# MB1137.net
KiCad netlist of a schematic drawn in Altium Designer
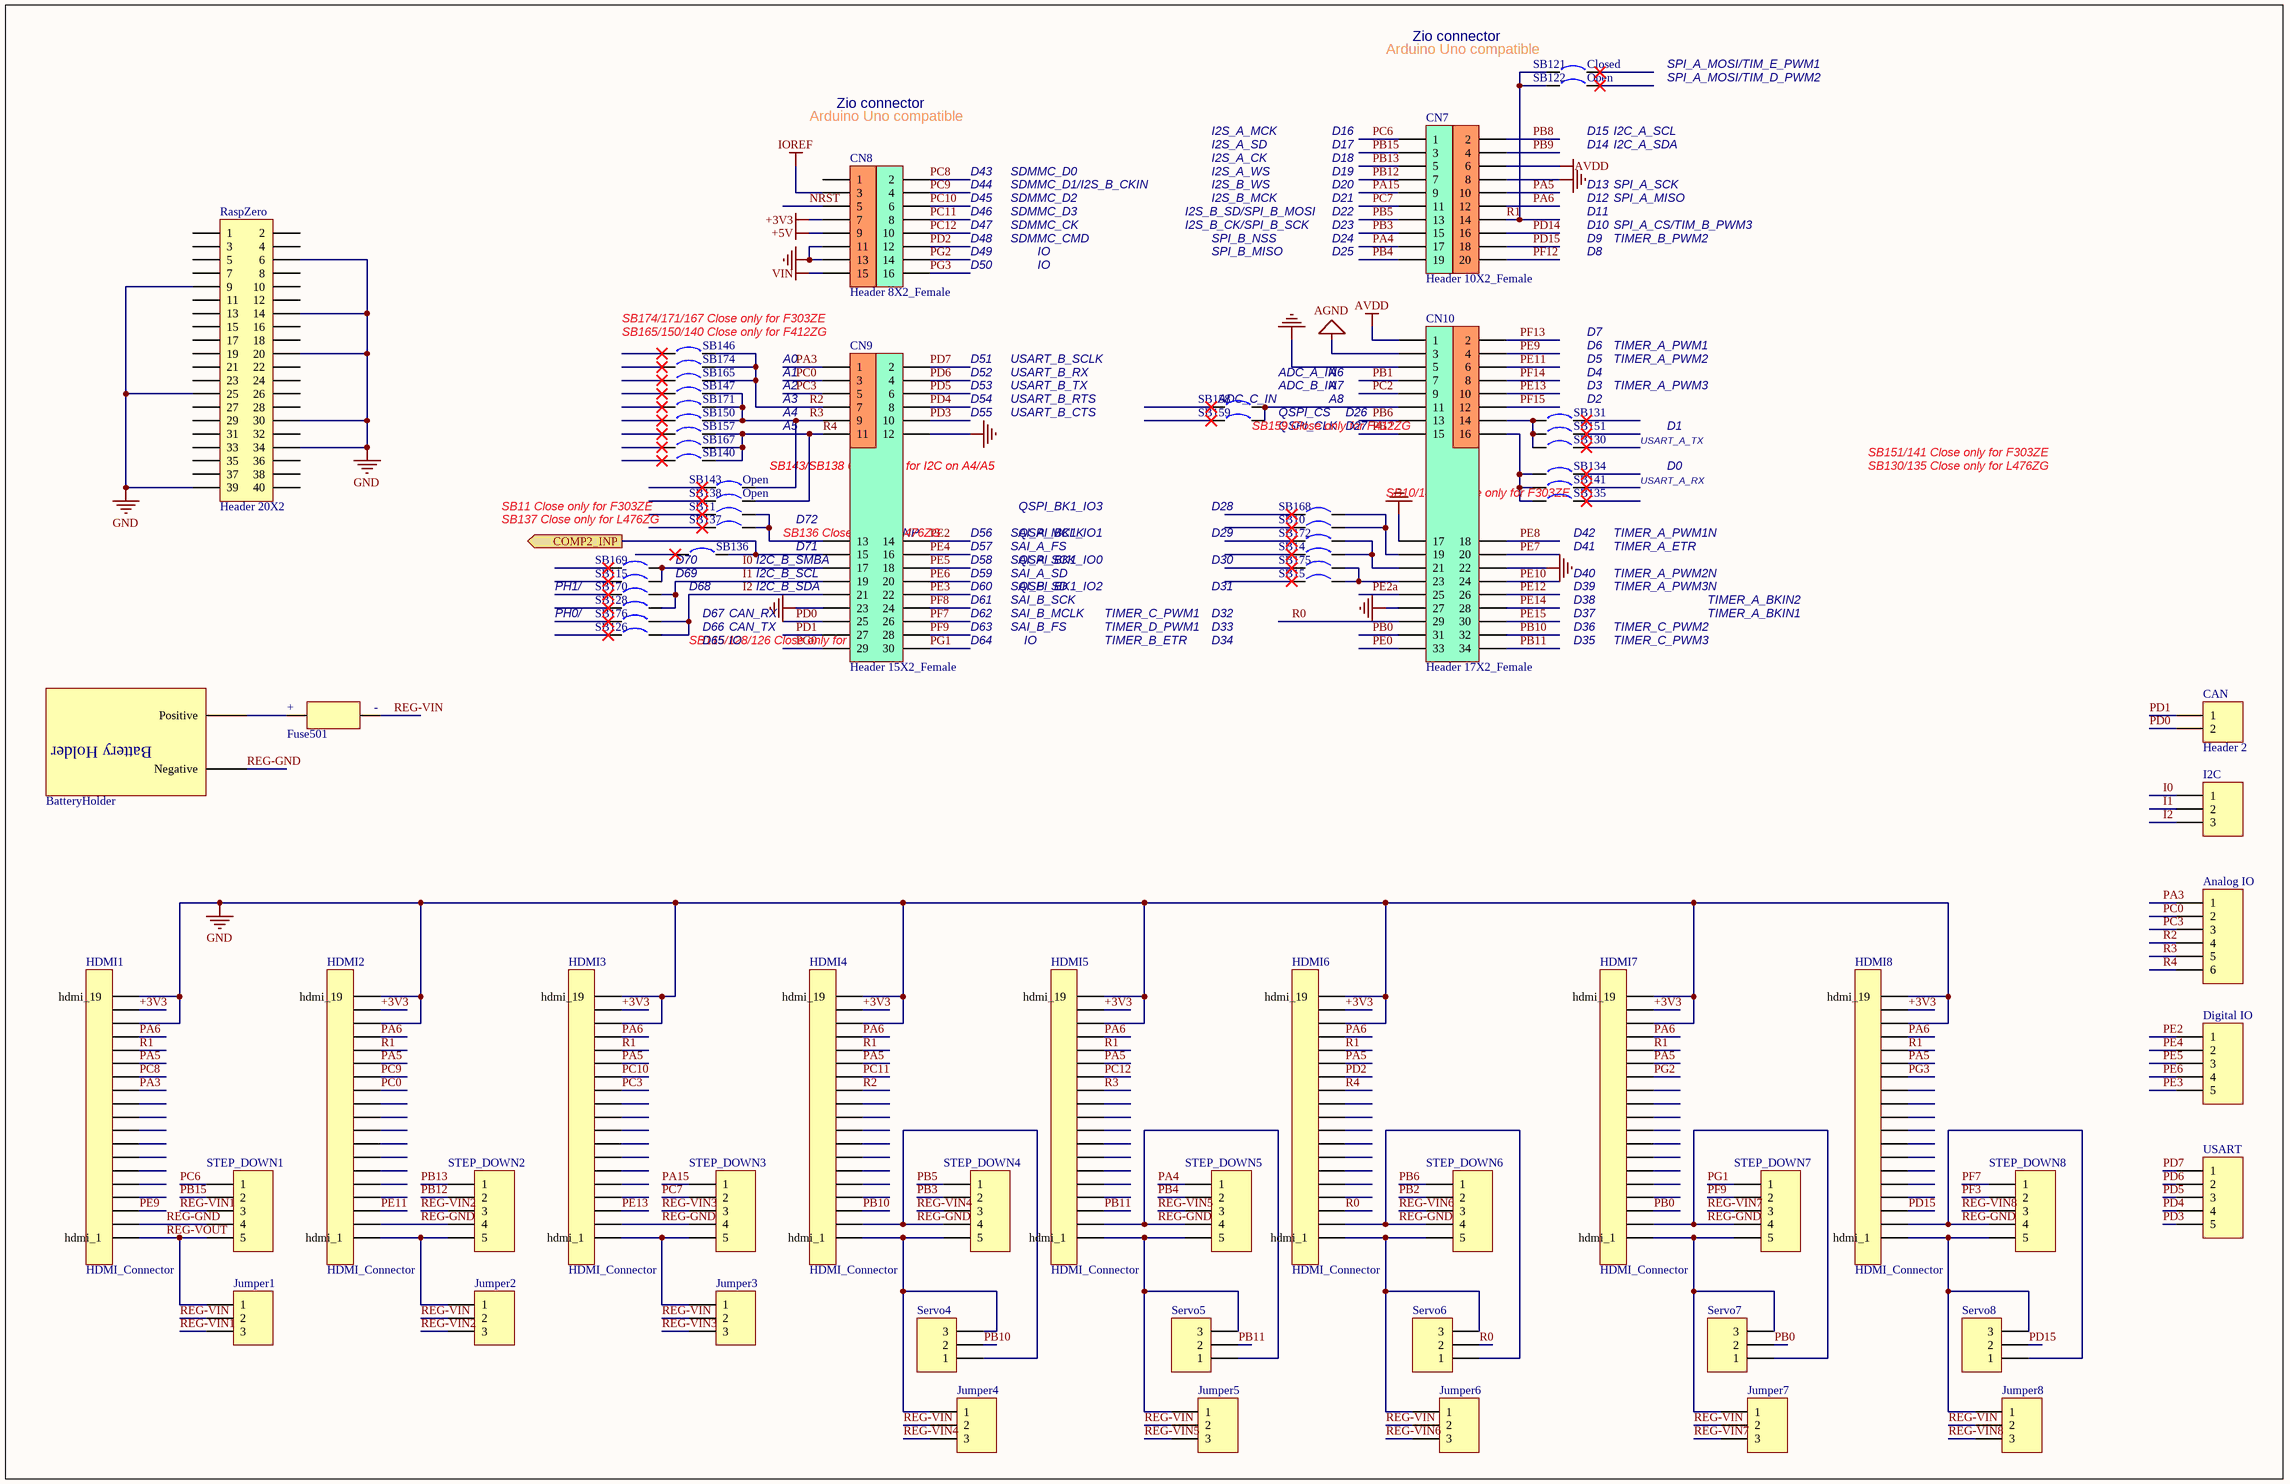
[diagram p0: MB1137.SchDoc]

(export (version "E")
  (design (tool "Eeschema 10.0.6"))
  (components
    (comp (ref "Analog IO")
      (value "Header 6")
      (footprint "HDR1X6")
      (description "Header, 6-Pin")
      (fields (field (name "PUBLISHER") "Altium Limited"))
      (libsource (lib "Miscellaneous Connectors") (part "Header 6"))
    )
    (comp (ref "BatteryHolder")
      (value "BatteryHolder")
      (footprint "SOIC127P370X135-2N")
      (libsource (lib "BatteryHolder") (part "BatteryHolder"))
    )
    (comp (ref "CAN")
      (value "Header 2")
      (footprint "HDR1X2")
      (description "Header, 2-Pin")
      (fields (field (name "PUBLISHER") "Altium Limited"))
      (libsource (lib "Miscellaneous Connectors") (part "Header 2"))
    )
    (comp (ref "CN7")
      (value "Header 10X2_Female")
      (footprint "HDR_10x2_2R54_V_F")
      (description "Header, 10-Pin, Dual row,female")
      (fields (field (name "PUBLISHER") "Altium Limited"))
      (libsource (lib "MB1137") (part "Header 10X2_Female"))
    )
    (comp (ref "CN8")
      (value "Header 8X2_Female")
      (footprint "HDR_8x2_2R54_V_F")
      (description "Header, 8-Pin, Dual row,female")
      (fields (field (name "PUBLISHER") "Altium Limited"))
      (libsource (lib "MB1137") (part "Header 8X2_Female"))
    )
    (comp (ref "CN9")
      (value "Header 15X2_Female")
      (footprint "HDR_15x2_2R54_V_F")
      (description "Header, 15-Pin, Dual row,female")
      (fields (field (name "PUBLISHER") "Altium Limited"))
      (libsource (lib "MB1137") (part "Header 15X2_Female"))
    )
    (comp (ref "CN10")
      (value "Header 17X2_Female")
      (footprint "HDR_17x2_2R54_V_F")
      (description "Header, 17-Pin, Dual row,female")
      (fields (field (name "PUBLISHER") "Altium Limited"))
      (libsource (lib "MB1137") (part "Header 17X2_Female"))
    )
    (comp (ref "Digital IO")
      (value "Header 5")
      (footprint "HDR1X5")
      (description "Header, 5-Pin")
      (fields (field (name "PUBLISHER") "Altium Limited"))
      (libsource (lib "Miscellaneous Connectors") (part "Header 5"))
    )
    (comp (ref "Fuse501") (value "Fuse501") (libsource (lib "Fuse501") (part "Fuse501")))
    (comp (ref "HDMI1")
      (value "HDMI_Connector")
      (footprint "HDMI-CONNECTOR")
      (libsource (lib "hdmiConnector-typeA") (part "HDMI_Connector"))
    )
    (comp (ref "HDMI2")
      (value "HDMI_Connector")
      (footprint "HDMI-CONNECTOR")
      (libsource (lib "hdmiConnector-typeA") (part "HDMI_Connector"))
    )
    (comp (ref "HDMI3")
      (value "HDMI_Connector")
      (footprint "HDMI-CONNECTOR")
      (libsource (lib "hdmiConnector-typeA") (part "HDMI_Connector"))
    )
    (comp (ref "HDMI4")
      (value "HDMI_Connector")
      (footprint "HDMI-CONNECTOR")
      (libsource (lib "hdmiConnector-typeA") (part "HDMI_Connector"))
    )
    (comp (ref "HDMI5")
      (value "HDMI_Connector")
      (footprint "HDMI-CONNECTOR")
      (libsource (lib "hdmiConnector-typeA") (part "HDMI_Connector"))
    )
    (comp (ref "HDMI6")
      (value "HDMI_Connector")
      (footprint "HDMI-CONNECTOR")
      (libsource (lib "hdmiConnector-typeA") (part "HDMI_Connector"))
    )
    (comp (ref "HDMI7")
      (value "HDMI_Connector")
      (footprint "HDMI-CONNECTOR")
      (libsource (lib "hdmiConnector-typeA") (part "HDMI_Connector"))
    )
    (comp (ref "HDMI8")
      (value "HDMI_Connector")
      (footprint "HDMI-CONNECTOR")
      (libsource (lib "hdmiConnector-typeA") (part "HDMI_Connector"))
    )
    (comp (ref "I2C")
      (value "Header 3")
      (footprint "HDR1X3")
      (description "Header, 3-Pin")
      (fields (field (name "PUBLISHER") "Altium Limited"))
      (libsource (lib "Miscellaneous Connectors") (part "Header 3"))
    )
    (comp (ref "Jumper1")
      (value "Header 3")
      (footprint "HDR1X3")
      (description "Header, 3-Pin")
      (fields (field (name "PUBLISHER") "Altium Limited"))
      (libsource (lib "Miscellaneous Connectors") (part "Header 3"))
    )
    (comp (ref "Jumper2")
      (value "Header 3")
      (footprint "HDR1X3")
      (description "Header, 3-Pin")
      (fields (field (name "PUBLISHER") "Altium Limited"))
      (libsource (lib "Miscellaneous Connectors") (part "Header 3"))
    )
    (comp (ref "Jumper3")
      (value "Header 3")
      (footprint "HDR1X3")
      (description "Header, 3-Pin")
      (fields (field (name "PUBLISHER") "Altium Limited"))
      (libsource (lib "Miscellaneous Connectors") (part "Header 3"))
    )
    (comp (ref "Jumper4")
      (value "Header 3")
      (footprint "HDR1X3")
      (description "Header, 3-Pin")
      (fields (field (name "PUBLISHER") "Altium Limited"))
      (libsource (lib "Miscellaneous Connectors") (part "Header 3"))
    )
    (comp (ref "Jumper5")
      (value "Header 3")
      (footprint "HDR1X3")
      (description "Header, 3-Pin")
      (fields (field (name "PUBLISHER") "Altium Limited"))
      (libsource (lib "Miscellaneous Connectors") (part "Header 3"))
    )
    (comp (ref "Jumper6")
      (value "Header 3")
      (footprint "HDR1X3")
      (description "Header, 3-Pin")
      (fields (field (name "PUBLISHER") "Altium Limited"))
      (libsource (lib "Miscellaneous Connectors") (part "Header 3"))
    )
    (comp (ref "Jumper7")
      (value "Header 3")
      (footprint "HDR1X3")
      (description "Header, 3-Pin")
      (fields (field (name "PUBLISHER") "Altium Limited"))
      (libsource (lib "Miscellaneous Connectors") (part "Header 3"))
    )
    (comp (ref "Jumper8")
      (value "Header 3")
      (footprint "HDR1X3")
      (description "Header, 3-Pin")
      (fields (field (name "PUBLISHER") "Altium Limited"))
      (libsource (lib "Miscellaneous Connectors") (part "Header 3"))
    )
    (comp (ref "RaspZero")
      (value "Header 20X2")
      (footprint "HDR2X20")
      (description "Header, 20-Pin, Dual row")
      (fields (field (name "PUBLISHER") "Altium Limited"))
      (libsource (lib "Miscellaneous Connectors") (part "Header 20X2"))
    )
    (comp (ref "SB10")
      (value "Circuit Breaker")
      (footprint "SB_0603")
      (fields (field (name "PUBLISHER") "Altium Limited"))
      (libsource (lib "") (part "Circuit Breaker_1"))
    )
    (comp (ref "SB11")
      (value "Circuit Breaker")
      (footprint "SB_0603")
      (fields (field (name "PUBLISHER") "Altium Limited"))
      (libsource (lib "MCD_TOOLS") (part "Circuit Breaker"))
    )
    (comp (ref "SB14")
      (value "Circuit Breaker")
      (footprint "SB_0603")
      (fields (field (name "PUBLISHER") "Altium Limited"))
      (libsource (lib "") (part "Circuit Breaker_1"))
    )
    (comp (ref "SB15")
      (value "Circuit Breaker")
      (footprint "SB_0603")
      (fields (field (name "PUBLISHER") "Altium Limited"))
      (libsource (lib "") (part "Circuit Breaker_1"))
    )
    (comp (ref "SB115")
      (value "Circuit Breaker")
      (footprint "SB_0603")
      (fields (field (name "PUBLISHER") "Altium Limited"))
      (libsource (lib "MCD_TOOLS") (part "Circuit Breaker"))
    )
    (comp (ref "SB121")
      (value "Closed")
      (footprint "SB_0603")
      (description "Circuit Breaker")
      (fields (field (name "PUBLISHER") "Altium Limited"))
      (libsource (lib "MB1167") (part "Circuit Breaker_close"))
    )
    (comp (ref "SB122")
      (value "Open")
      (footprint "SB_0603")
      (description "Circuit Breaker")
      (fields (field (name "PUBLISHER") "Altium Limited"))
      (libsource (lib "MB1167") (part "Circuit Breaker"))
    )
    (comp (ref "SB126")
      (value "Circuit Breaker")
      (footprint "SB_0603")
      (fields (field (name "PUBLISHER") "Altium Limited"))
      (libsource (lib "MCD_TOOLS") (part "Circuit Breaker"))
    )
    (comp (ref "SB128")
      (value "Circuit Breaker")
      (footprint "SB_0603")
      (fields (field (name "PUBLISHER") "Altium Limited"))
      (libsource (lib "MCD_TOOLS") (part "Circuit Breaker"))
    )
    (comp (ref "SB130")
      (value "Circuit Breaker")
      (footprint "SB_0603")
      (fields (field (name "PUBLISHER") "Altium Limited"))
      (libsource (lib "MCD_TOOLS") (part "Circuit Breaker"))
    )
    (comp (ref "SB131")
      (value "Circuit Breaker")
      (footprint "SB_0603")
      (fields (field (name "PUBLISHER") "Altium Limited"))
      (libsource (lib "MCD_TOOLS") (part "Circuit Breaker"))
    )
    (comp (ref "SB134")
      (value "Circuit Breaker")
      (footprint "SB_0603")
      (fields (field (name "PUBLISHER") "Altium Limited"))
      (libsource (lib "MCD_TOOLS") (part "Circuit Breaker"))
    )
    (comp (ref "SB135")
      (value "Circuit Breaker")
      (footprint "SB_0603")
      (fields (field (name "PUBLISHER") "Altium Limited"))
      (libsource (lib "MCD_TOOLS") (part "Circuit Breaker"))
    )
    (comp (ref "SB136")
      (value "Circuit Breaker")
      (footprint "SB_0603")
      (fields (field (name "PUBLISHER") "Altium Limited"))
      (libsource (lib "MCD_TOOLS") (part "Circuit Breaker"))
    )
    (comp (ref "SB137")
      (value "Circuit Breaker")
      (footprint "SB_0603")
      (fields (field (name "PUBLISHER") "Altium Limited"))
      (libsource (lib "MCD_TOOLS") (part "Circuit Breaker"))
    )
    (comp (ref "SB138")
      (value "Open")
      (footprint "SB_0603")
      (description "Circuit Breaker")
      (fields (field (name "PUBLISHER") "Altium Limited"))
      (libsource (lib "") (part "Circuit Breaker_1"))
    )
    (comp (ref "SB140")
      (value "Circuit Breaker")
      (footprint "SB_0603")
      (fields (field (name "PUBLISHER") "Altium Limited"))
      (libsource (lib "MCD_TOOLS") (part "Circuit Breaker"))
    )
    (comp (ref "SB141")
      (value "Circuit Breaker")
      (footprint "SB_0603")
      (fields (field (name "PUBLISHER") "Altium Limited"))
      (libsource (lib "MCD_TOOLS") (part "Circuit Breaker"))
    )
    (comp (ref "SB143")
      (value "Open")
      (footprint "SB_0603")
      (description "Circuit Breaker")
      (fields (field (name "PUBLISHER") "Altium Limited"))
      (libsource (lib "") (part "Circuit Breaker_1"))
    )
    (comp (ref "SB146")
      (value "Circuit Breaker")
      (footprint "SB_0603")
      (fields (field (name "PUBLISHER") "Altium Limited"))
      (libsource (lib "MCD_TOOLS") (part "Circuit Breaker"))
    )
    (comp (ref "SB147")
      (value "Circuit Breaker")
      (footprint "SB_0603")
      (fields (field (name "PUBLISHER") "Altium Limited"))
      (libsource (lib "MCD_TOOLS") (part "Circuit Breaker"))
    )
    (comp (ref "SB150")
      (value "Circuit Breaker")
      (footprint "SB_0603")
      (fields (field (name "PUBLISHER") "Altium Limited"))
      (libsource (lib "MCD_TOOLS") (part "Circuit Breaker"))
    )
    (comp (ref "SB151")
      (value "Circuit Breaker")
      (footprint "SB_0603")
      (fields (field (name "PUBLISHER") "Altium Limited"))
      (libsource (lib "MCD_TOOLS") (part "Circuit Breaker"))
    )
    (comp (ref "SB157")
      (value "Circuit Breaker")
      (footprint "SB_0603")
      (fields (field (name "PUBLISHER") "Altium Limited"))
      (libsource (lib "MCD_TOOLS") (part "Circuit Breaker"))
    )
    (comp (ref "SB158")
      (value "Circuit Breaker")
      (footprint "SB_0603")
      (fields (field (name "PUBLISHER") "Altium Limited"))
      (libsource (lib "") (part "Circuit Breaker_1"))
    )
    (comp (ref "SB159")
      (value "Circuit Breaker")
      (footprint "SB_0603")
      (fields (field (name "PUBLISHER") "Altium Limited"))
      (libsource (lib "") (part "Circuit Breaker_1"))
    )
    (comp (ref "SB165")
      (value "Circuit Breaker")
      (footprint "SB_0603")
      (fields (field (name "PUBLISHER") "Altium Limited"))
      (libsource (lib "MCD_TOOLS") (part "Circuit Breaker"))
    )
    (comp (ref "SB167")
      (value "Circuit Breaker")
      (footprint "SB_0603")
      (fields (field (name "PUBLISHER") "Altium Limited"))
      (libsource (lib "MCD_TOOLS") (part "Circuit Breaker"))
    )
    (comp (ref "SB168")
      (value "Circuit Breaker")
      (footprint "SB_0603")
      (fields (field (name "PUBLISHER") "Altium Limited"))
      (libsource (lib "") (part "Circuit Breaker_1"))
    )
    (comp (ref "SB169")
      (value "Circuit Breaker")
      (footprint "SB_0603")
      (fields (field (name "PUBLISHER") "Altium Limited"))
      (libsource (lib "MCD_TOOLS") (part "Circuit Breaker"))
    )
    (comp (ref "SB170")
      (value "Circuit Breaker")
      (footprint "SB_0603")
      (fields (field (name "PUBLISHER") "Altium Limited"))
      (libsource (lib "MCD_TOOLS") (part "Circuit Breaker"))
    )
    (comp (ref "SB171")
      (value "Circuit Breaker")
      (footprint "SB_0603")
      (fields (field (name "PUBLISHER") "Altium Limited"))
      (libsource (lib "MCD_TOOLS") (part "Circuit Breaker"))
    )
    (comp (ref "SB172")
      (value "Circuit Breaker")
      (footprint "SB_0603")
      (fields (field (name "PUBLISHER") "Altium Limited"))
      (libsource (lib "") (part "Circuit Breaker_1"))
    )
    (comp (ref "SB174")
      (value "Circuit Breaker")
      (footprint "SB_0603")
      (fields (field (name "PUBLISHER") "Altium Limited"))
      (libsource (lib "MCD_TOOLS") (part "Circuit Breaker"))
    )
    (comp (ref "SB175")
      (value "Circuit Breaker")
      (footprint "SB_0603")
      (fields (field (name "PUBLISHER") "Altium Limited"))
      (libsource (lib "") (part "Circuit Breaker_1"))
    )
    (comp (ref "SB176")
      (value "Circuit Breaker")
      (footprint "SB_0603")
      (fields (field (name "PUBLISHER") "Altium Limited"))
      (libsource (lib "MCD_TOOLS") (part "Circuit Breaker"))
    )
    (comp (ref "Servo4")
      (value "Header 3")
      (footprint "HDR1X3")
      (description "Header, 3-Pin")
      (fields (field (name "PUBLISHER") "Altium Limited"))
      (libsource (lib "") (part "Header 3_1"))
    )
    (comp (ref "Servo5")
      (value "Header 3")
      (footprint "HDR1X3")
      (description "Header, 3-Pin")
      (fields (field (name "PUBLISHER") "Altium Limited"))
      (libsource (lib "") (part "Header 3_1"))
    )
    (comp (ref "Servo6")
      (value "Header 3")
      (footprint "HDR1X3")
      (description "Header, 3-Pin")
      (fields (field (name "PUBLISHER") "Altium Limited"))
      (libsource (lib "") (part "Header 3_1"))
    )
    (comp (ref "Servo7")
      (value "Header 3")
      (footprint "HDR1X3")
      (description "Header, 3-Pin")
      (fields (field (name "PUBLISHER") "Altium Limited"))
      (libsource (lib "") (part "Header 3_1"))
    )
    (comp (ref "Servo8")
      (value "Header 3")
      (footprint "HDR1X3")
      (description "Header, 3-Pin")
      (fields (field (name "PUBLISHER") "Altium Limited"))
      (libsource (lib "") (part "Header 3_1"))
    )
    (comp (ref "STEP_DOWN1")
      (value "Header 5")
      (footprint "HDR1X5")
      (description "Header, 5-Pin")
      (fields (field (name "PUBLISHER") "Altium Limited"))
      (libsource (lib "Miscellaneous Connectors") (part "Header 5"))
    )
    (comp (ref "STEP_DOWN2")
      (value "Header 5")
      (footprint "HDR1X5")
      (description "Header, 5-Pin")
      (fields (field (name "PUBLISHER") "Altium Limited"))
      (libsource (lib "Miscellaneous Connectors") (part "Header 5"))
    )
    (comp (ref "STEP_DOWN3")
      (value "Header 5")
      (footprint "HDR1X5")
      (description "Header, 5-Pin")
      (fields (field (name "PUBLISHER") "Altium Limited"))
      (libsource (lib "Miscellaneous Connectors") (part "Header 5"))
    )
    (comp (ref "STEP_DOWN4")
      (value "Header 5")
      (footprint "HDR1X5")
      (description "Header, 5-Pin")
      (fields (field (name "PUBLISHER") "Altium Limited"))
      (libsource (lib "Miscellaneous Connectors") (part "Header 5"))
    )
    (comp (ref "STEP_DOWN5")
      (value "Header 5")
      (footprint "HDR1X5")
      (description "Header, 5-Pin")
      (fields (field (name "PUBLISHER") "Altium Limited"))
      (libsource (lib "Miscellaneous Connectors") (part "Header 5"))
    )
    (comp (ref "STEP_DOWN6")
      (value "Header 5")
      (footprint "HDR1X5")
      (description "Header, 5-Pin")
      (fields (field (name "PUBLISHER") "Altium Limited"))
      (libsource (lib "Miscellaneous Connectors") (part "Header 5"))
    )
    (comp (ref "STEP_DOWN7")
      (value "Header 5")
      (footprint "HDR1X5")
      (description "Header, 5-Pin")
      (fields (field (name "PUBLISHER") "Altium Limited"))
      (libsource (lib "Miscellaneous Connectors") (part "Header 5"))
    )
    (comp (ref "STEP_DOWN8")
      (value "Header 5")
      (footprint "HDR1X5")
      (description "Header, 5-Pin")
      (fields (field (name "PUBLISHER") "Altium Limited"))
      (libsource (lib "Miscellaneous Connectors") (part "Header 5"))
    )
    (comp (ref "USART")
      (value "Header 5")
      (footprint "HDR1X5")
      (description "Header, 5-Pin")
      (fields (field (name "PUBLISHER") "Altium Limited"))
      (libsource (lib "Miscellaneous Connectors") (part "Header 5"))
    )
  )
  (nets
    (net (code "1") (name "+3V3") (class "Default")
      (node (ref "CN8") (pin "7") (pinfunction "7_7") (pintype "passive"))
      (node (ref "HDMI1") (pin "hdmi_18") (pinfunction "hdmi_18_hdmi_18") (pintype "passive"))
      (node (ref "HDMI2") (pin "hdmi_18") (pinfunction "hdmi_18_hdmi_18") (pintype "passive"))
      (node (ref "HDMI3") (pin "hdmi_18") (pinfunction "hdmi_18_hdmi_18") (pintype "passive"))
      (node (ref "HDMI4") (pin "hdmi_18") (pinfunction "hdmi_18_hdmi_18") (pintype "passive"))
      (node (ref "HDMI5") (pin "hdmi_18") (pinfunction "hdmi_18_hdmi_18") (pintype "passive"))
      (node (ref "HDMI6") (pin "hdmi_18") (pinfunction "hdmi_18_hdmi_18") (pintype "passive"))
      (node (ref "HDMI7") (pin "hdmi_18") (pinfunction "hdmi_18_hdmi_18") (pintype "passive"))
      (node (ref "HDMI8") (pin "hdmi_18") (pinfunction "hdmi_18_hdmi_18") (pintype "passive"))
    )
    (net (code "2") (name "+5V") (class "Default")
      (node (ref "CN8") (pin "9") (pinfunction "9_9") (pintype "passive"))
    )
    (net (code "3") (name "/COMP2_INP") (class "Default")
      (node (ref "CN9") (pin "15") (pinfunction "15_15") (pintype "passive"))
      (node (ref "SB136") (pin "1") (pinfunction "1_1") (pintype "passive"))
    )
    (net (code "4") (name "/I0") (class "Default")
      (node (ref "CN9") (pin "17") (pinfunction "17_17") (pintype "passive"))
      (node (ref "I2C") (pin "1") (pinfunction "1_1") (pintype "passive"))
      (node (ref "SB115") (pin "1") (pinfunction "1_1") (pintype "passive"))
      (node (ref "SB169") (pin "1") (pinfunction "1_1") (pintype "passive"))
    )
    (net (code "5") (name "/I1") (class "Default")
      (node (ref "CN9") (pin "19") (pinfunction "19_19") (pintype "passive"))
      (node (ref "I2C") (pin "2") (pinfunction "2_2") (pintype "passive"))
      (node (ref "SB128") (pin "1") (pinfunction "1_1") (pintype "passive"))
      (node (ref "SB170") (pin "1") (pinfunction "1_1") (pintype "passive"))
    )
    (net (code "6") (name "/I2") (class "Default")
      (node (ref "CN9") (pin "21") (pinfunction "21_21") (pintype "passive"))
      (node (ref "I2C") (pin "3") (pinfunction "3_3") (pintype "passive"))
      (node (ref "SB126") (pin "1") (pinfunction "1_1") (pintype "passive"))
      (node (ref "SB176") (pin "1") (pinfunction "1_1") (pintype "passive"))
    )
    (net (code "7") (name "/NRST") (class "Default")
      (node (ref "CN8") (pin "5") (pinfunction "5_5") (pintype "passive"))
    )
    (net (code "8") (name "/PA3") (class "Default")
      (node (ref "Analog IO") (pin "1") (pinfunction "1_1") (pintype "passive"))
      (node (ref "CN9") (pin "1") (pinfunction "1_1") (pintype "passive"))
      (node (ref "HDMI1") (pin "hdmi_12") (pinfunction "hdmi_12_hdmi_12") (pintype "passive"))
    )
    (net (code "9") (name "/PA4") (class "Default")
      (node (ref "CN7") (pin "17") (pinfunction "17_17") (pintype "passive"))
      (node (ref "STEP_DOWN5") (pin "1") (pinfunction "1_1") (pintype "passive"))
    )
    (net (code "10") (name "/PA5") (class "Default")
      (node (ref "CN7") (pin "10") (pinfunction "10_10") (pintype "passive"))
      (node (ref "HDMI1") (pin "hdmi_14") (pinfunction "hdmi_14_hdmi_14") (pintype "passive"))
      (node (ref "HDMI2") (pin "hdmi_14") (pinfunction "hdmi_14_hdmi_14") (pintype "passive"))
      (node (ref "HDMI3") (pin "hdmi_14") (pinfunction "hdmi_14_hdmi_14") (pintype "passive"))
      (node (ref "HDMI4") (pin "hdmi_14") (pinfunction "hdmi_14_hdmi_14") (pintype "passive"))
      (node (ref "HDMI5") (pin "hdmi_14") (pinfunction "hdmi_14_hdmi_14") (pintype "passive"))
      (node (ref "HDMI6") (pin "hdmi_14") (pinfunction "hdmi_14_hdmi_14") (pintype "passive"))
      (node (ref "HDMI7") (pin "hdmi_14") (pinfunction "hdmi_14_hdmi_14") (pintype "passive"))
      (node (ref "HDMI8") (pin "hdmi_14") (pinfunction "hdmi_14_hdmi_14") (pintype "passive"))
    )
    (net (code "11") (name "/PA6") (class "Default")
      (node (ref "CN7") (pin "12") (pinfunction "12_12") (pintype "passive"))
      (node (ref "HDMI1") (pin "hdmi_16") (pinfunction "hdmi_16_hdmi_16") (pintype "passive"))
      (node (ref "HDMI2") (pin "hdmi_16") (pinfunction "hdmi_16_hdmi_16") (pintype "passive"))
      (node (ref "HDMI3") (pin "hdmi_16") (pinfunction "hdmi_16_hdmi_16") (pintype "passive"))
      (node (ref "HDMI4") (pin "hdmi_16") (pinfunction "hdmi_16_hdmi_16") (pintype "passive"))
      (node (ref "HDMI5") (pin "hdmi_16") (pinfunction "hdmi_16_hdmi_16") (pintype "passive"))
      (node (ref "HDMI6") (pin "hdmi_16") (pinfunction "hdmi_16_hdmi_16") (pintype "passive"))
      (node (ref "HDMI7") (pin "hdmi_16") (pinfunction "hdmi_16_hdmi_16") (pintype "passive"))
      (node (ref "HDMI8") (pin "hdmi_16") (pinfunction "hdmi_16_hdmi_16") (pintype "passive"))
    )
    (net (code "12") (name "/PA15") (class "Default")
      (node (ref "CN7") (pin "9") (pinfunction "9_9") (pintype "passive"))
      (node (ref "STEP_DOWN3") (pin "1") (pinfunction "1_1") (pintype "passive"))
    )
    (net (code "13") (name "/PB0") (class "Default")
      (node (ref "CN10") (pin "31") (pinfunction "31_31") (pintype "passive"))
      (node (ref "HDMI7") (pin "hdmi_3") (pinfunction "hdmi_3_hdmi_3") (pintype "passive"))
      (node (ref "Servo7") (pin "2") (pinfunction "2_2") (pintype "passive"))
    )
    (net (code "14") (name "/PB1") (class "Default")
      (node (ref "CN10") (pin "7") (pinfunction "7_7") (pintype "passive"))
    )
    (net (code "15") (name "/PB2") (class "Default")
      (node (ref "CN10") (pin "15") (pinfunction "15_15") (pintype "passive"))
      (node (ref "STEP_DOWN6") (pin "2") (pinfunction "2_2") (pintype "passive"))
    )
    (net (code "16") (name "/PB3") (class "Default")
      (node (ref "CN7") (pin "15") (pinfunction "15_15") (pintype "passive"))
      (node (ref "STEP_DOWN4") (pin "2") (pinfunction "2_2") (pintype "passive"))
    )
    (net (code "17") (name "/PB4") (class "Default")
      (node (ref "CN7") (pin "19") (pinfunction "19_19") (pintype "passive"))
      (node (ref "STEP_DOWN5") (pin "2") (pinfunction "2_2") (pintype "passive"))
    )
    (net (code "18") (name "/PB5") (class "Default")
      (node (ref "CN7") (pin "13") (pinfunction "13_13") (pintype "passive"))
      (node (ref "STEP_DOWN4") (pin "1") (pinfunction "1_1") (pintype "passive"))
    )
    (net (code "19") (name "/PB6") (class "Default")
      (node (ref "CN10") (pin "13") (pinfunction "13_13") (pintype "passive"))
      (node (ref "STEP_DOWN6") (pin "1") (pinfunction "1_1") (pintype "passive"))
    )
    (net (code "20") (name "/PB8") (class "Default")
      (node (ref "CN7") (pin "2") (pinfunction "2_2") (pintype "passive"))
    )
    (net (code "21") (name "/PB9") (class "Default")
      (node (ref "CN7") (pin "4") (pinfunction "4_4") (pintype "passive"))
    )
    (net (code "22") (name "/PB10") (class "Default")
      (node (ref "CN10") (pin "32") (pinfunction "32_32") (pintype "passive"))
      (node (ref "HDMI4") (pin "hdmi_3") (pinfunction "hdmi_3_hdmi_3") (pintype "passive"))
      (node (ref "Servo4") (pin "2") (pinfunction "2_2") (pintype "passive"))
    )
    (net (code "23") (name "/PB11") (class "Default")
      (node (ref "CN10") (pin "34") (pinfunction "34_34") (pintype "passive"))
      (node (ref "HDMI5") (pin "hdmi_3") (pinfunction "hdmi_3_hdmi_3") (pintype "passive"))
      (node (ref "Servo5") (pin "2") (pinfunction "2_2") (pintype "passive"))
    )
    (net (code "24") (name "/PB12") (class "Default")
      (node (ref "CN7") (pin "7") (pinfunction "7_7") (pintype "passive"))
      (node (ref "STEP_DOWN2") (pin "2") (pinfunction "2_2") (pintype "passive"))
    )
    (net (code "25") (name "/PB13") (class "Default")
      (node (ref "CN7") (pin "5") (pinfunction "5_5") (pintype "passive"))
      (node (ref "STEP_DOWN2") (pin "1") (pinfunction "1_1") (pintype "passive"))
    )
    (net (code "26") (name "/PB15") (class "Default")
      (node (ref "CN7") (pin "3") (pinfunction "3_3") (pintype "passive"))
      (node (ref "STEP_DOWN1") (pin "2") (pinfunction "2_2") (pintype "passive"))
    )
    (net (code "27") (name "/PC0") (class "Default")
      (node (ref "Analog IO") (pin "2") (pinfunction "2_2") (pintype "passive"))
      (node (ref "CN9") (pin "3") (pinfunction "3_3") (pintype "passive"))
      (node (ref "HDMI2") (pin "hdmi_12") (pinfunction "hdmi_12_hdmi_12") (pintype "passive"))
    )
    (net (code "28") (name "/PC2") (class "Default")
      (node (ref "CN10") (pin "9") (pinfunction "9_9") (pintype "passive"))
    )
    (net (code "29") (name "/PC3") (class "Default")
      (node (ref "Analog IO") (pin "3") (pinfunction "3_3") (pintype "passive"))
      (node (ref "CN9") (pin "5") (pinfunction "5_5") (pintype "passive"))
      (node (ref "HDMI3") (pin "hdmi_12") (pinfunction "hdmi_12_hdmi_12") (pintype "passive"))
    )
    (net (code "30") (name "/PC6") (class "Default")
      (node (ref "CN7") (pin "1") (pinfunction "1_1") (pintype "passive"))
      (node (ref "STEP_DOWN1") (pin "1") (pinfunction "1_1") (pintype "passive"))
    )
    (net (code "31") (name "/PC7") (class "Default")
      (node (ref "CN7") (pin "11") (pinfunction "11_11") (pintype "passive"))
      (node (ref "STEP_DOWN3") (pin "2") (pinfunction "2_2") (pintype "passive"))
    )
    (net (code "32") (name "/PC8") (class "Default")
      (node (ref "CN8") (pin "2") (pinfunction "2_2") (pintype "passive"))
      (node (ref "HDMI1") (pin "hdmi_13") (pinfunction "hdmi_13_hdmi_13") (pintype "passive"))
    )
    (net (code "33") (name "/PC9") (class "Default")
      (node (ref "CN8") (pin "4") (pinfunction "4_4") (pintype "passive"))
      (node (ref "HDMI2") (pin "hdmi_13") (pinfunction "hdmi_13_hdmi_13") (pintype "passive"))
    )
    (net (code "34") (name "/PC10") (class "Default")
      (node (ref "CN8") (pin "6") (pinfunction "6_6") (pintype "passive"))
      (node (ref "HDMI3") (pin "hdmi_13") (pinfunction "hdmi_13_hdmi_13") (pintype "passive"))
    )
    (net (code "35") (name "/PC11") (class "Default")
      (node (ref "CN8") (pin "8") (pinfunction "8_8") (pintype "passive"))
      (node (ref "HDMI4") (pin "hdmi_13") (pinfunction "hdmi_13_hdmi_13") (pintype "passive"))
    )
    (net (code "36") (name "/PC12") (class "Default")
      (node (ref "CN8") (pin "10") (pinfunction "10_10") (pintype "passive"))
      (node (ref "HDMI5") (pin "hdmi_13") (pinfunction "hdmi_13_hdmi_13") (pintype "passive"))
    )
    (net (code "37") (name "/PD0") (class "Default")
      (node (ref "CAN") (pin "2") (pinfunction "2_2") (pintype "passive"))
      (node (ref "CN9") (pin "25") (pinfunction "25_25") (pintype "passive"))
    )
    (net (code "38") (name "/PD1") (class "Default")
      (node (ref "CAN") (pin "1") (pinfunction "1_1") (pintype "passive"))
      (node (ref "CN9") (pin "27") (pinfunction "27_27") (pintype "passive"))
    )
    (net (code "39") (name "/PD2") (class "Default")
      (node (ref "CN8") (pin "12") (pinfunction "12_12") (pintype "passive"))
      (node (ref "HDMI6") (pin "hdmi_13") (pinfunction "hdmi_13_hdmi_13") (pintype "passive"))
    )
    (net (code "40") (name "/PD3") (class "Default")
      (node (ref "CN9") (pin "10") (pinfunction "10_10") (pintype "passive"))
      (node (ref "USART") (pin "5") (pinfunction "5_5") (pintype "passive"))
    )
    (net (code "41") (name "/PD4") (class "Default")
      (node (ref "CN9") (pin "8") (pinfunction "8_8") (pintype "passive"))
      (node (ref "USART") (pin "4") (pinfunction "4_4") (pintype "passive"))
    )
    (net (code "42") (name "/PD5") (class "Default")
      (node (ref "CN9") (pin "6") (pinfunction "6_6") (pintype "passive"))
      (node (ref "USART") (pin "3") (pinfunction "3_3") (pintype "passive"))
    )
    (net (code "43") (name "/PD6") (class "Default")
      (node (ref "CN9") (pin "4") (pinfunction "4_4") (pintype "passive"))
      (node (ref "USART") (pin "2") (pinfunction "2_2") (pintype "passive"))
    )
    (net (code "44") (name "/PD7") (class "Default")
      (node (ref "CN9") (pin "2") (pinfunction "2_2") (pintype "passive"))
      (node (ref "USART") (pin "1") (pinfunction "1_1") (pintype "passive"))
    )
    (net (code "45") (name "/PD14") (class "Default")
      (node (ref "CN7") (pin "16") (pinfunction "16_16") (pintype "passive"))
    )
    (net (code "46") (name "/PD15") (class "Default")
      (node (ref "CN7") (pin "18") (pinfunction "18_18") (pintype "passive"))
      (node (ref "HDMI8") (pin "hdmi_3") (pinfunction "hdmi_3_hdmi_3") (pintype "passive"))
      (node (ref "Servo8") (pin "2") (pinfunction "2_2") (pintype "passive"))
    )
    (net (code "47") (name "/PE0") (class "Default")
      (node (ref "CN10") (pin "33") (pinfunction "33_33") (pintype "passive"))
    )
    (net (code "48") (name "/PE2") (class "Default")
      (node (ref "CN9") (pin "14") (pinfunction "14_14") (pintype "passive"))
      (node (ref "Digital IO") (pin "1") (pinfunction "1_1") (pintype "passive"))
    )
    (net (code "49") (name "/PE2a") (class "Default")
      (node (ref "CN10") (pin "25") (pinfunction "25_25") (pintype "passive"))
    )
    (net (code "50") (name "/PE3") (class "Default")
      (node (ref "CN9") (pin "22") (pinfunction "22_22") (pintype "passive"))
      (node (ref "Digital IO") (pin "5") (pinfunction "5_5") (pintype "passive"))
    )
    (net (code "51") (name "/PE4") (class "Default")
      (node (ref "CN9") (pin "16") (pinfunction "16_16") (pintype "passive"))
      (node (ref "Digital IO") (pin "2") (pinfunction "2_2") (pintype "passive"))
    )
    (net (code "52") (name "/PE5") (class "Default")
      (node (ref "CN9") (pin "18") (pinfunction "18_18") (pintype "passive"))
      (node (ref "Digital IO") (pin "3") (pinfunction "3_3") (pintype "passive"))
    )
    (net (code "53") (name "/PE6") (class "Default")
      (node (ref "CN9") (pin "20") (pinfunction "20_20") (pintype "passive"))
      (node (ref "Digital IO") (pin "4") (pinfunction "4_4") (pintype "passive"))
    )
    (net (code "54") (name "/PE7") (class "Default")
      (node (ref "CN10") (pin "20") (pinfunction "20_20") (pintype "passive"))
    )
    (net (code "55") (name "/PE8") (class "Default")
      (node (ref "CN10") (pin "18") (pinfunction "18_18") (pintype "passive"))
    )
    (net (code "56") (name "/PE9") (class "Default")
      (node (ref "CN10") (pin "4") (pinfunction "4_4") (pintype "passive"))
      (node (ref "HDMI1") (pin "hdmi_3") (pinfunction "hdmi_3_hdmi_3") (pintype "passive"))
    )
    (net (code "57") (name "/PE10") (class "Default")
      (node (ref "CN10") (pin "24") (pinfunction "24_24") (pintype "passive"))
    )
    (net (code "58") (name "/PE11") (class "Default")
      (node (ref "CN10") (pin "6") (pinfunction "6_6") (pintype "passive"))
      (node (ref "HDMI2") (pin "hdmi_3") (pinfunction "hdmi_3_hdmi_3") (pintype "passive"))
    )
    (net (code "59") (name "/PE12") (class "Default")
      (node (ref "CN10") (pin "26") (pinfunction "26_26") (pintype "passive"))
    )
    (net (code "60") (name "/PE13") (class "Default")
      (node (ref "CN10") (pin "10") (pinfunction "10_10") (pintype "passive"))
      (node (ref "HDMI3") (pin "hdmi_3") (pinfunction "hdmi_3_hdmi_3") (pintype "passive"))
    )
    (net (code "61") (name "/PE14") (class "Default")
      (node (ref "CN10") (pin "28") (pinfunction "28_28") (pintype "passive"))
    )
    (net (code "62") (name "/PE15") (class "Default")
      (node (ref "CN10") (pin "30") (pinfunction "30_30") (pintype "passive"))
    )
    (net (code "63") (name "/PF3") (class "Default")
      (node (ref "STEP_DOWN8") (pin "2") (pinfunction "2_2") (pintype "passive"))
    )
    (net (code "64") (name "/PF7") (class "Default")
      (node (ref "CN9") (pin "26") (pinfunction "26_26") (pintype "passive"))
      (node (ref "STEP_DOWN8") (pin "1") (pinfunction "1_1") (pintype "passive"))
    )
    (net (code "65") (name "/PF8") (class "Default")
      (node (ref "CN9") (pin "24") (pinfunction "24_24") (pintype "passive"))
    )
    (net (code "66") (name "/PF9") (class "Default")
      (node (ref "CN9") (pin "28") (pinfunction "28_28") (pintype "passive"))
      (node (ref "STEP_DOWN7") (pin "2") (pinfunction "2_2") (pintype "passive"))
    )
    (net (code "67") (name "/PF12") (class "Default")
      (node (ref "CN7") (pin "20") (pinfunction "20_20") (pintype "passive"))
    )
    (net (code "68") (name "/PF13") (class "Default")
      (node (ref "CN10") (pin "2") (pinfunction "2_2") (pintype "passive"))
    )
    (net (code "69") (name "/PF14") (class "Default")
      (node (ref "CN10") (pin "8") (pinfunction "8_8") (pintype "passive"))
    )
    (net (code "70") (name "/PF15") (class "Default")
      (node (ref "CN10") (pin "12") (pinfunction "12_12") (pintype "passive"))
    )
    (net (code "71") (name "/PG0") (class "Default")
      (node (ref "CN9") (pin "29") (pinfunction "29_29") (pintype "passive"))
    )
    (net (code "72") (name "/PG1") (class "Default")
      (node (ref "CN9") (pin "30") (pinfunction "30_30") (pintype "passive"))
      (node (ref "STEP_DOWN7") (pin "1") (pinfunction "1_1") (pintype "passive"))
    )
    (net (code "73") (name "/PG2") (class "Default")
      (node (ref "CN8") (pin "14") (pinfunction "14_14") (pintype "passive"))
      (node (ref "HDMI7") (pin "hdmi_13") (pinfunction "hdmi_13_hdmi_13") (pintype "passive"))
    )
    (net (code "74") (name "/PG3") (class "Default")
      (node (ref "CN8") (pin "16") (pinfunction "16_16") (pintype "passive"))
      (node (ref "HDMI8") (pin "hdmi_13") (pinfunction "hdmi_13_hdmi_13") (pintype "passive"))
    )
    (net (code "75") (name "/R0") (class "Default")
      (node (ref "CN10") (pin "29") (pinfunction "29_29") (pintype "passive"))
      (node (ref "HDMI6") (pin "hdmi_3") (pinfunction "hdmi_3_hdmi_3") (pintype "passive"))
      (node (ref "Servo6") (pin "2") (pinfunction "2_2") (pintype "passive"))
    )
    (net (code "76") (name "/R1") (class "Default")
      (node (ref "CN7") (pin "14") (pinfunction "14_14") (pintype "passive"))
      (node (ref "HDMI1") (pin "hdmi_15") (pinfunction "hdmi_15_hdmi_15") (pintype "passive"))
      (node (ref "HDMI2") (pin "hdmi_15") (pinfunction "hdmi_15_hdmi_15") (pintype "passive"))
      (node (ref "HDMI3") (pin "hdmi_15") (pinfunction "hdmi_15_hdmi_15") (pintype "passive"))
      (node (ref "HDMI4") (pin "hdmi_15") (pinfunction "hdmi_15_hdmi_15") (pintype "passive"))
      (node (ref "HDMI5") (pin "hdmi_15") (pinfunction "hdmi_15_hdmi_15") (pintype "passive"))
      (node (ref "HDMI6") (pin "hdmi_15") (pinfunction "hdmi_15_hdmi_15") (pintype "passive"))
      (node (ref "HDMI7") (pin "hdmi_15") (pinfunction "hdmi_15_hdmi_15") (pintype "passive"))
      (node (ref "HDMI8") (pin "hdmi_15") (pinfunction "hdmi_15_hdmi_15") (pintype "passive"))
      (node (ref "SB121") (pin "1") (pinfunction "1_1") (pintype "passive"))
      (node (ref "SB122") (pin "1") (pinfunction "1_1") (pintype "passive"))
    )
    (net (code "77") (name "/R2") (class "Default")
      (node (ref "Analog IO") (pin "4") (pinfunction "4_4") (pintype "passive"))
      (node (ref "CN9") (pin "7") (pinfunction "7_7") (pintype "passive"))
      (node (ref "HDMI4") (pin "hdmi_12") (pinfunction "hdmi_12_hdmi_12") (pintype "passive"))
      (node (ref "SB146") (pin "1") (pinfunction "1_1") (pintype "passive"))
      (node (ref "SB165") (pin "1") (pinfunction "1_1") (pintype "passive"))
      (node (ref "SB174") (pin "1") (pinfunction "1_1") (pintype "passive"))
    )
    (net (code "78") (name "/R3") (class "Default")
      (node (ref "Analog IO") (pin "5") (pinfunction "5_5") (pintype "passive"))
      (node (ref "CN9") (pin "9") (pinfunction "9_9") (pintype "passive"))
      (node (ref "HDMI5") (pin "hdmi_12") (pinfunction "hdmi_12_hdmi_12") (pintype "passive"))
      (node (ref "SB143") (pin "1") (pinfunction "1_1") (pintype "passive"))
      (node (ref "SB147") (pin "1") (pinfunction "1_1") (pintype "passive"))
      (node (ref "SB150") (pin "1") (pinfunction "1_1") (pintype "passive"))
      (node (ref "SB171") (pin "1") (pinfunction "1_1") (pintype "passive"))
    )
    (net (code "79") (name "/R4") (class "Default")
      (node (ref "Analog IO") (pin "6") (pinfunction "6_6") (pintype "passive"))
      (node (ref "CN9") (pin "11") (pinfunction "11_11") (pintype "passive"))
      (node (ref "HDMI6") (pin "hdmi_12") (pinfunction "hdmi_12_hdmi_12") (pintype "passive"))
      (node (ref "SB138") (pin "1") (pinfunction "1_1") (pintype "passive"))
      (node (ref "SB140") (pin "1") (pinfunction "1_1") (pintype "passive"))
      (node (ref "SB157") (pin "1") (pinfunction "1_1") (pintype "passive"))
      (node (ref "SB167") (pin "1") (pinfunction "1_1") (pintype "passive"))
    )
    (net (code "80") (name "/REG-GND") (class "Default")
      (node (ref "BatteryHolder") (pin "1n") (pinfunction "Negative_1n") (pintype "passive"))
      (node (ref "HDMI1") (pin "hdmi_2") (pinfunction "hdmi_2_hdmi_2") (pintype "passive"))
      (node (ref "HDMI2") (pin "hdmi_2") (pinfunction "hdmi_2_hdmi_2") (pintype "passive"))
      (node (ref "HDMI3") (pin "hdmi_2") (pinfunction "hdmi_2_hdmi_2") (pintype "passive"))
      (node (ref "HDMI4") (pin "hdmi_2") (pinfunction "hdmi_2_hdmi_2") (pintype "passive"))
      (node (ref "HDMI5") (pin "hdmi_2") (pinfunction "hdmi_2_hdmi_2") (pintype "passive"))
      (node (ref "HDMI6") (pin "hdmi_2") (pinfunction "hdmi_2_hdmi_2") (pintype "passive"))
      (node (ref "HDMI7") (pin "hdmi_2") (pinfunction "hdmi_2_hdmi_2") (pintype "passive"))
      (node (ref "HDMI8") (pin "hdmi_2") (pinfunction "hdmi_2_hdmi_2") (pintype "passive"))
      (node (ref "STEP_DOWN1") (pin "4") (pinfunction "4_4") (pintype "passive"))
      (node (ref "STEP_DOWN2") (pin "4") (pinfunction "4_4") (pintype "passive"))
      (node (ref "STEP_DOWN3") (pin "4") (pinfunction "4_4") (pintype "passive"))
      (node (ref "STEP_DOWN4") (pin "4") (pinfunction "4_4") (pintype "passive"))
      (node (ref "STEP_DOWN5") (pin "4") (pinfunction "4_4") (pintype "passive"))
      (node (ref "STEP_DOWN6") (pin "4") (pinfunction "4_4") (pintype "passive"))
      (node (ref "STEP_DOWN7") (pin "4") (pinfunction "4_4") (pintype "passive"))
      (node (ref "STEP_DOWN8") (pin "4") (pinfunction "4_4") (pintype "passive"))
      (node (ref "Servo4") (pin "1") (pinfunction "1_1") (pintype "passive"))
      (node (ref "Servo5") (pin "1") (pinfunction "1_1") (pintype "passive"))
      (node (ref "Servo6") (pin "1") (pinfunction "1_1") (pintype "passive"))
      (node (ref "Servo7") (pin "1") (pinfunction "1_1") (pintype "passive"))
      (node (ref "Servo8") (pin "1") (pinfunction "1_1") (pintype "passive"))
    )
    (net (code "81") (name "/REG-VIN") (class "Default")
      (node (ref "Fuse501") (pin "Fuse-") (pinfunction "Fuse-_Fuse-") (pintype "passive"))
      (node (ref "Jumper1") (pin "2") (pinfunction "2_2") (pintype "passive"))
      (node (ref "Jumper2") (pin "2") (pinfunction "2_2") (pintype "passive"))
      (node (ref "Jumper3") (pin "2") (pinfunction "2_2") (pintype "passive"))
      (node (ref "Jumper4") (pin "2") (pinfunction "2_2") (pintype "passive"))
      (node (ref "Jumper5") (pin "2") (pinfunction "2_2") (pintype "passive"))
      (node (ref "Jumper6") (pin "2") (pinfunction "2_2") (pintype "passive"))
      (node (ref "Jumper7") (pin "2") (pinfunction "2_2") (pintype "passive"))
      (node (ref "Jumper8") (pin "2") (pinfunction "2_2") (pintype "passive"))
    )
    (net (code "82") (name "/REG-VIN1") (class "Default")
      (node (ref "Jumper1") (pin "3") (pinfunction "3_3") (pintype "passive"))
      (node (ref "STEP_DOWN1") (pin "3") (pinfunction "3_3") (pintype "passive"))
    )
    (net (code "83") (name "/REG-VIN2") (class "Default")
      (node (ref "Jumper2") (pin "3") (pinfunction "3_3") (pintype "passive"))
      (node (ref "STEP_DOWN2") (pin "3") (pinfunction "3_3") (pintype "passive"))
    )
    (net (code "84") (name "/REG-VIN3") (class "Default")
      (node (ref "Jumper3") (pin "3") (pinfunction "3_3") (pintype "passive"))
      (node (ref "STEP_DOWN3") (pin "3") (pinfunction "3_3") (pintype "passive"))
    )
    (net (code "85") (name "/REG-VIN4") (class "Default")
      (node (ref "Jumper4") (pin "3") (pinfunction "3_3") (pintype "passive"))
      (node (ref "STEP_DOWN4") (pin "3") (pinfunction "3_3") (pintype "passive"))
    )
    (net (code "86") (name "/REG-VIN5") (class "Default")
      (node (ref "Jumper5") (pin "3") (pinfunction "3_3") (pintype "passive"))
      (node (ref "STEP_DOWN5") (pin "3") (pinfunction "3_3") (pintype "passive"))
    )
    (net (code "87") (name "/REG-VIN6") (class "Default")
      (node (ref "Jumper6") (pin "3") (pinfunction "3_3") (pintype "passive"))
      (node (ref "STEP_DOWN6") (pin "3") (pinfunction "3_3") (pintype "passive"))
    )
    (net (code "88") (name "/REG-VIN7") (class "Default")
      (node (ref "Jumper7") (pin "3") (pinfunction "3_3") (pintype "passive"))
      (node (ref "STEP_DOWN7") (pin "3") (pinfunction "3_3") (pintype "passive"))
    )
    (net (code "89") (name "/REG-VIN8") (class "Default")
      (node (ref "Jumper8") (pin "3") (pinfunction "3_3") (pintype "passive"))
      (node (ref "STEP_DOWN8") (pin "3") (pinfunction "3_3") (pintype "passive"))
    )
    (net (code "90") (name "/REG-VOUT") (class "Default")
      (node (ref "HDMI1") (pin "hdmi_1") (pinfunction "hdmi_1_hdmi_1") (pintype "passive"))
      (node (ref "Jumper1") (pin "1") (pinfunction "1_1") (pintype "passive"))
      (node (ref "STEP_DOWN1") (pin "5") (pinfunction "5_5") (pintype "passive"))
    )
    (net (code "91") (name "AGND") (class "Default")
      (node (ref "CN10") (pin "3") (pinfunction "3_3") (pintype "passive"))
    )
    (net (code "92") (name "AVDD") (class "Default")
      (node (ref "CN10") (pin "1") (pinfunction "1_1") (pintype "passive"))
      (node (ref "CN7") (pin "6") (pinfunction "6_6") (pintype "passive"))
    )
    (net (code "93") (name "GND") (class "Default")
      (node (ref "CN10") (pin "17") (pinfunction "17_17") (pintype "passive"))
      (node (ref "CN10") (pin "22") (pinfunction "22_22") (pintype "passive"))
      (node (ref "CN10") (pin "27") (pinfunction "27_27") (pintype "passive"))
      (node (ref "CN10") (pin "5") (pinfunction "5_5") (pintype "passive"))
      (node (ref "CN7") (pin "8") (pinfunction "8_8") (pintype "passive"))
      (node (ref "CN8") (pin "11") (pinfunction "11_11") (pintype "passive"))
      (node (ref "CN8") (pin "13") (pinfunction "13_13") (pintype "passive"))
      (node (ref "CN9") (pin "12") (pinfunction "12_12") (pintype "passive"))
      (node (ref "CN9") (pin "23") (pinfunction "23_23") (pintype "passive"))
      (node (ref "HDMI1") (pin "hdmi_17") (pinfunction "hdmi_17_hdmi_17") (pintype "passive"))
      (node (ref "HDMI1") (pin "hdmi_19") (pinfunction "hdmi_19_hdmi_19") (pintype "passive"))
      (node (ref "HDMI2") (pin "hdmi_17") (pinfunction "hdmi_17_hdmi_17") (pintype "passive"))
      (node (ref "HDMI2") (pin "hdmi_19") (pinfunction "hdmi_19_hdmi_19") (pintype "passive"))
      (node (ref "HDMI3") (pin "hdmi_17") (pinfunction "hdmi_17_hdmi_17") (pintype "passive"))
      (node (ref "HDMI3") (pin "hdmi_19") (pinfunction "hdmi_19_hdmi_19") (pintype "passive"))
      (node (ref "HDMI4") (pin "hdmi_17") (pinfunction "hdmi_17_hdmi_17") (pintype "passive"))
      (node (ref "HDMI4") (pin "hdmi_19") (pinfunction "hdmi_19_hdmi_19") (pintype "passive"))
      (node (ref "HDMI5") (pin "hdmi_17") (pinfunction "hdmi_17_hdmi_17") (pintype "passive"))
      (node (ref "HDMI5") (pin "hdmi_19") (pinfunction "hdmi_19_hdmi_19") (pintype "passive"))
      (node (ref "HDMI6") (pin "hdmi_17") (pinfunction "hdmi_17_hdmi_17") (pintype "passive"))
      (node (ref "HDMI6") (pin "hdmi_19") (pinfunction "hdmi_19_hdmi_19") (pintype "passive"))
      (node (ref "HDMI7") (pin "hdmi_17") (pinfunction "hdmi_17_hdmi_17") (pintype "passive"))
      (node (ref "HDMI7") (pin "hdmi_19") (pinfunction "hdmi_19_hdmi_19") (pintype "passive"))
      (node (ref "HDMI8") (pin "hdmi_17") (pinfunction "hdmi_17_hdmi_17") (pintype "passive"))
      (node (ref "HDMI8") (pin "hdmi_19") (pinfunction "hdmi_19_hdmi_19") (pintype "passive"))
      (node (ref "RaspZero") (pin "14") (pinfunction "14_14") (pintype "passive"))
      (node (ref "RaspZero") (pin "20") (pinfunction "20_20") (pintype "passive"))
      (node (ref "RaspZero") (pin "25") (pinfunction "25_25") (pintype "passive"))
      (node (ref "RaspZero") (pin "30") (pinfunction "30_30") (pintype "passive"))
      (node (ref "RaspZero") (pin "34") (pinfunction "34_34") (pintype "passive"))
      (node (ref "RaspZero") (pin "39") (pinfunction "39_39") (pintype "passive"))
      (node (ref "RaspZero") (pin "6") (pinfunction "6_6") (pintype "passive"))
      (node (ref "RaspZero") (pin "9") (pinfunction "9_9") (pintype "passive"))
    )
    (net (code "94") (name "IOREF") (class "Default")
      (node (ref "CN8") (pin "3") (pinfunction "3_3") (pintype "passive"))
    )
    (net (code "95") (name "Net-(BatteryHolder-Positive)") (class "Default")
      (node (ref "BatteryHolder") (pin "1p") (pinfunction "Positive_1p") (pintype "passive"))
      (node (ref "Fuse501") (pin "Fuse+") (pinfunction "Fuse+_Fuse+") (pintype "passive"))
    )
    (net (code "96") (name "Net-(CN9-Pad13)") (class "Default")
      (node (ref "CN9") (pin "13") (pinfunction "13_13") (pintype "passive"))
      (node (ref "SB11") (pin "1") (pinfunction "1_1") (pintype "passive"))
      (node (ref "SB137") (pin "1") (pinfunction "1_1") (pintype "passive"))
    )
    (net (code "97") (name "Net-(CN10-Pad11)") (class "Default")
      (node (ref "CN10") (pin "11") (pinfunction "11_11") (pintype "passive"))
      (node (ref "SB158") (pin "2") (pinfunction "2_2") (pintype "passive"))
      (node (ref "SB159") (pin "2") (pinfunction "2_2") (pintype "passive"))
    )
    (net (code "98") (name "Net-(CN10-Pad14)") (class "Default")
      (node (ref "CN10") (pin "14") (pinfunction "14_14") (pintype "passive"))
      (node (ref "SB130") (pin "2") (pinfunction "2_2") (pintype "passive"))
      (node (ref "SB131") (pin "2") (pinfunction "2_2") (pintype "passive"))
      (node (ref "SB151") (pin "2") (pinfunction "2_2") (pintype "passive"))
    )
    (net (code "99") (name "Net-(CN10-Pad16)") (class "Default")
      (node (ref "CN10") (pin "16") (pinfunction "16_16") (pintype "passive"))
      (node (ref "SB134") (pin "2") (pinfunction "2_2") (pintype "passive"))
      (node (ref "SB135") (pin "2") (pinfunction "2_2") (pintype "passive"))
      (node (ref "SB141") (pin "2") (pinfunction "2_2") (pintype "passive"))
    )
    (net (code "100") (name "Net-(CN10-Pad19)") (class "Default")
      (node (ref "CN10") (pin "19") (pinfunction "19_19") (pintype "passive"))
      (node (ref "SB10") (pin "2") (pinfunction "2_2") (pintype "passive"))
      (node (ref "SB168") (pin "2") (pinfunction "2_2") (pintype "passive"))
    )
    (net (code "101") (name "Net-(CN10-Pad21)") (class "Default")
      (node (ref "CN10") (pin "21") (pinfunction "21_21") (pintype "passive"))
      (node (ref "SB14") (pin "2") (pinfunction "2_2") (pintype "passive"))
      (node (ref "SB172") (pin "2") (pinfunction "2_2") (pintype "passive"))
    )
    (net (code "102") (name "Net-(CN10-Pad23)") (class "Default")
      (node (ref "CN10") (pin "23") (pinfunction "23_23") (pintype "passive"))
      (node (ref "SB15") (pin "2") (pinfunction "2_2") (pintype "passive"))
      (node (ref "SB175") (pin "2") (pinfunction "2_2") (pintype "passive"))
    )
    (net (code "103") (name "Net-(HDMI2-Padhdmi_1)") (class "Default")
      (node (ref "HDMI2") (pin "hdmi_1") (pinfunction "hdmi_1_hdmi_1") (pintype "passive"))
      (node (ref "Jumper2") (pin "1") (pinfunction "1_1") (pintype "passive"))
      (node (ref "STEP_DOWN2") (pin "5") (pinfunction "5_5") (pintype "passive"))
    )
    (net (code "104") (name "Net-(HDMI3-Padhdmi_1)") (class "Default")
      (node (ref "HDMI3") (pin "hdmi_1") (pinfunction "hdmi_1_hdmi_1") (pintype "passive"))
      (node (ref "Jumper3") (pin "1") (pinfunction "1_1") (pintype "passive"))
      (node (ref "STEP_DOWN3") (pin "5") (pinfunction "5_5") (pintype "passive"))
    )
    (net (code "105") (name "Net-(HDMI4-Padhdmi_1)") (class "Default")
      (node (ref "HDMI4") (pin "hdmi_1") (pinfunction "hdmi_1_hdmi_1") (pintype "passive"))
      (node (ref "Jumper4") (pin "1") (pinfunction "1_1") (pintype "passive"))
      (node (ref "STEP_DOWN4") (pin "5") (pinfunction "5_5") (pintype "passive"))
      (node (ref "Servo4") (pin "3") (pinfunction "3_3") (pintype "passive"))
    )
    (net (code "106") (name "Net-(HDMI5-Padhdmi_1)") (class "Default")
      (node (ref "HDMI5") (pin "hdmi_1") (pinfunction "hdmi_1_hdmi_1") (pintype "passive"))
      (node (ref "Jumper5") (pin "1") (pinfunction "1_1") (pintype "passive"))
      (node (ref "STEP_DOWN5") (pin "5") (pinfunction "5_5") (pintype "passive"))
      (node (ref "Servo5") (pin "3") (pinfunction "3_3") (pintype "passive"))
    )
    (net (code "107") (name "Net-(HDMI6-Padhdmi_1)") (class "Default")
      (node (ref "HDMI6") (pin "hdmi_1") (pinfunction "hdmi_1_hdmi_1") (pintype "passive"))
      (node (ref "Jumper6") (pin "1") (pinfunction "1_1") (pintype "passive"))
      (node (ref "STEP_DOWN6") (pin "5") (pinfunction "5_5") (pintype "passive"))
      (node (ref "Servo6") (pin "3") (pinfunction "3_3") (pintype "passive"))
    )
    (net (code "108") (name "Net-(HDMI7-Padhdmi_1)") (class "Default")
      (node (ref "HDMI7") (pin "hdmi_1") (pinfunction "hdmi_1_hdmi_1") (pintype "passive"))
      (node (ref "Jumper7") (pin "1") (pinfunction "1_1") (pintype "passive"))
      (node (ref "STEP_DOWN7") (pin "5") (pinfunction "5_5") (pintype "passive"))
      (node (ref "Servo7") (pin "3") (pinfunction "3_3") (pintype "passive"))
    )
    (net (code "109") (name "Net-(HDMI8-Padhdmi_1)") (class "Default")
      (node (ref "HDMI8") (pin "hdmi_1") (pinfunction "hdmi_1_hdmi_1") (pintype "passive"))
      (node (ref "Jumper8") (pin "1") (pinfunction "1_1") (pintype "passive"))
      (node (ref "STEP_DOWN8") (pin "5") (pinfunction "5_5") (pintype "passive"))
      (node (ref "Servo8") (pin "3") (pinfunction "3_3") (pintype "passive"))
    )
    (net (code "110") (name "VIN") (class "Default")
      (node (ref "CN8") (pin "15") (pinfunction "15_15") (pintype "passive"))
    )
    (net (code "111") (name "unconnected-(CN8-Pad1)") (class "Default")
      (node (ref "CN8") (pin "1") (pinfunction "1_1") (pintype "passive"))
    )
    (net (code "112") (name "unconnected-(HDMI1-Padhdmi_4)") (class "Default")
      (node (ref "HDMI1") (pin "hdmi_4") (pinfunction "hdmi_4_hdmi_4") (pintype "passive"))
    )
    (net (code "113") (name "unconnected-(HDMI1-Padhdmi_5)") (class "Default")
      (node (ref "HDMI1") (pin "hdmi_5") (pinfunction "hdmi_5_hdmi_5") (pintype "passive"))
    )
    (net (code "114") (name "unconnected-(HDMI1-Padhdmi_6)") (class "Default")
      (node (ref "HDMI1") (pin "hdmi_6") (pinfunction "hdmi_6_hdmi_6") (pintype "passive"))
    )
    (net (code "115") (name "unconnected-(HDMI1-Padhdmi_7)") (class "Default")
      (node (ref "HDMI1") (pin "hdmi_7") (pinfunction "hdmi_7_hdmi_7") (pintype "passive"))
    )
    (net (code "116") (name "unconnected-(HDMI1-Padhdmi_8)") (class "Default")
      (node (ref "HDMI1") (pin "hdmi_8") (pinfunction "hdmi_8_hdmi_8") (pintype "passive"))
    )
    (net (code "117") (name "unconnected-(HDMI1-Padhdmi_9)") (class "Default")
      (node (ref "HDMI1") (pin "hdmi_9") (pinfunction "hdmi_9_hdmi_9") (pintype "passive"))
    )
    (net (code "118") (name "unconnected-(HDMI1-Padhdmi_10)") (class "Default")
      (node (ref "HDMI1") (pin "hdmi_10") (pinfunction "hdmi_10_hdmi_10") (pintype "passive"))
    )
    (net (code "119") (name "unconnected-(HDMI1-Padhdmi_11)") (class "Default")
      (node (ref "HDMI1") (pin "hdmi_11") (pinfunction "hdmi_11_hdmi_11") (pintype "passive"))
    )
    (net (code "120") (name "unconnected-(HDMI2-Padhdmi_4)") (class "Default")
      (node (ref "HDMI2") (pin "hdmi_4") (pinfunction "hdmi_4_hdmi_4") (pintype "passive"))
    )
    (net (code "121") (name "unconnected-(HDMI2-Padhdmi_5)") (class "Default")
      (node (ref "HDMI2") (pin "hdmi_5") (pinfunction "hdmi_5_hdmi_5") (pintype "passive"))
    )
    (net (code "122") (name "unconnected-(HDMI2-Padhdmi_6)") (class "Default")
      (node (ref "HDMI2") (pin "hdmi_6") (pinfunction "hdmi_6_hdmi_6") (pintype "passive"))
    )
    (net (code "123") (name "unconnected-(HDMI2-Padhdmi_7)") (class "Default")
      (node (ref "HDMI2") (pin "hdmi_7") (pinfunction "hdmi_7_hdmi_7") (pintype "passive"))
    )
    (net (code "124") (name "unconnected-(HDMI2-Padhdmi_8)") (class "Default")
      (node (ref "HDMI2") (pin "hdmi_8") (pinfunction "hdmi_8_hdmi_8") (pintype "passive"))
    )
    (net (code "125") (name "unconnected-(HDMI2-Padhdmi_9)") (class "Default")
      (node (ref "HDMI2") (pin "hdmi_9") (pinfunction "hdmi_9_hdmi_9") (pintype "passive"))
    )
    (net (code "126") (name "unconnected-(HDMI2-Padhdmi_10)") (class "Default")
      (node (ref "HDMI2") (pin "hdmi_10") (pinfunction "hdmi_10_hdmi_10") (pintype "passive"))
    )
    (net (code "127") (name "unconnected-(HDMI2-Padhdmi_11)") (class "Default")
      (node (ref "HDMI2") (pin "hdmi_11") (pinfunction "hdmi_11_hdmi_11") (pintype "passive"))
    )
    (net (code "128") (name "unconnected-(HDMI3-Padhdmi_4)") (class "Default")
      (node (ref "HDMI3") (pin "hdmi_4") (pinfunction "hdmi_4_hdmi_4") (pintype "passive"))
    )
    (net (code "129") (name "unconnected-(HDMI3-Padhdmi_5)") (class "Default")
      (node (ref "HDMI3") (pin "hdmi_5") (pinfunction "hdmi_5_hdmi_5") (pintype "passive"))
    )
    (net (code "130") (name "unconnected-(HDMI3-Padhdmi_6)") (class "Default")
      (node (ref "HDMI3") (pin "hdmi_6") (pinfunction "hdmi_6_hdmi_6") (pintype "passive"))
    )
    (net (code "131") (name "unconnected-(HDMI3-Padhdmi_7)") (class "Default")
      (node (ref "HDMI3") (pin "hdmi_7") (pinfunction "hdmi_7_hdmi_7") (pintype "passive"))
    )
    (net (code "132") (name "unconnected-(HDMI3-Padhdmi_8)") (class "Default")
      (node (ref "HDMI3") (pin "hdmi_8") (pinfunction "hdmi_8_hdmi_8") (pintype "passive"))
    )
    (net (code "133") (name "unconnected-(HDMI3-Padhdmi_9)") (class "Default")
      (node (ref "HDMI3") (pin "hdmi_9") (pinfunction "hdmi_9_hdmi_9") (pintype "passive"))
    )
    (net (code "134") (name "unconnected-(HDMI3-Padhdmi_10)") (class "Default")
      (node (ref "HDMI3") (pin "hdmi_10") (pinfunction "hdmi_10_hdmi_10") (pintype "passive"))
    )
    (net (code "135") (name "unconnected-(HDMI3-Padhdmi_11)") (class "Default")
      (node (ref "HDMI3") (pin "hdmi_11") (pinfunction "hdmi_11_hdmi_11") (pintype "passive"))
    )
    (net (code "136") (name "unconnected-(HDMI4-Padhdmi_4)") (class "Default")
      (node (ref "HDMI4") (pin "hdmi_4") (pinfunction "hdmi_4_hdmi_4") (pintype "passive"))
    )
    (net (code "137") (name "unconnected-(HDMI4-Padhdmi_5)") (class "Default")
      (node (ref "HDMI4") (pin "hdmi_5") (pinfunction "hdmi_5_hdmi_5") (pintype "passive"))
    )
    (net (code "138") (name "unconnected-(HDMI4-Padhdmi_6)") (class "Default")
      (node (ref "HDMI4") (pin "hdmi_6") (pinfunction "hdmi_6_hdmi_6") (pintype "passive"))
    )
    (net (code "139") (name "unconnected-(HDMI4-Padhdmi_7)") (class "Default")
      (node (ref "HDMI4") (pin "hdmi_7") (pinfunction "hdmi_7_hdmi_7") (pintype "passive"))
    )
    (net (code "140") (name "unconnected-(HDMI4-Padhdmi_8)") (class "Default")
      (node (ref "HDMI4") (pin "hdmi_8") (pinfunction "hdmi_8_hdmi_8") (pintype "passive"))
    )
    (net (code "141") (name "unconnected-(HDMI4-Padhdmi_9)") (class "Default")
      (node (ref "HDMI4") (pin "hdmi_9") (pinfunction "hdmi_9_hdmi_9") (pintype "passive"))
    )
    (net (code "142") (name "unconnected-(HDMI4-Padhdmi_10)") (class "Default")
      (node (ref "HDMI4") (pin "hdmi_10") (pinfunction "hdmi_10_hdmi_10") (pintype "passive"))
    )
    (net (code "143") (name "unconnected-(HDMI4-Padhdmi_11)") (class "Default")
      (node (ref "HDMI4") (pin "hdmi_11") (pinfunction "hdmi_11_hdmi_11") (pintype "passive"))
    )
    (net (code "144") (name "unconnected-(HDMI5-Padhdmi_4)") (class "Default")
      (node (ref "HDMI5") (pin "hdmi_4") (pinfunction "hdmi_4_hdmi_4") (pintype "passive"))
    )
    (net (code "145") (name "unconnected-(HDMI5-Padhdmi_5)") (class "Default")
      (node (ref "HDMI5") (pin "hdmi_5") (pinfunction "hdmi_5_hdmi_5") (pintype "passive"))
    )
    (net (code "146") (name "unconnected-(HDMI5-Padhdmi_6)") (class "Default")
      (node (ref "HDMI5") (pin "hdmi_6") (pinfunction "hdmi_6_hdmi_6") (pintype "passive"))
    )
    (net (code "147") (name "unconnected-(HDMI5-Padhdmi_7)") (class "Default")
      (node (ref "HDMI5") (pin "hdmi_7") (pinfunction "hdmi_7_hdmi_7") (pintype "passive"))
    )
    (net (code "148") (name "unconnected-(HDMI5-Padhdmi_8)") (class "Default")
      (node (ref "HDMI5") (pin "hdmi_8") (pinfunction "hdmi_8_hdmi_8") (pintype "passive"))
    )
    (net (code "149") (name "unconnected-(HDMI5-Padhdmi_9)") (class "Default")
      (node (ref "HDMI5") (pin "hdmi_9") (pinfunction "hdmi_9_hdmi_9") (pintype "passive"))
    )
    (net (code "150") (name "unconnected-(HDMI5-Padhdmi_10)") (class "Default")
      (node (ref "HDMI5") (pin "hdmi_10") (pinfunction "hdmi_10_hdmi_10") (pintype "passive"))
    )
    (net (code "151") (name "unconnected-(HDMI5-Padhdmi_11)") (class "Default")
      (node (ref "HDMI5") (pin "hdmi_11") (pinfunction "hdmi_11_hdmi_11") (pintype "passive"))
    )
    (net (code "152") (name "unconnected-(HDMI6-Padhdmi_4)") (class "Default")
      (node (ref "HDMI6") (pin "hdmi_4") (pinfunction "hdmi_4_hdmi_4") (pintype "passive"))
    )
    (net (code "153") (name "unconnected-(HDMI6-Padhdmi_5)") (class "Default")
      (node (ref "HDMI6") (pin "hdmi_5") (pinfunction "hdmi_5_hdmi_5") (pintype "passive"))
    )
    (net (code "154") (name "unconnected-(HDMI6-Padhdmi_6)") (class "Default")
      (node (ref "HDMI6") (pin "hdmi_6") (pinfunction "hdmi_6_hdmi_6") (pintype "passive"))
    )
    (net (code "155") (name "unconnected-(HDMI6-Padhdmi_7)") (class "Default")
      (node (ref "HDMI6") (pin "hdmi_7") (pinfunction "hdmi_7_hdmi_7") (pintype "passive"))
    )
    (net (code "156") (name "unconnected-(HDMI6-Padhdmi_8)") (class "Default")
      (node (ref "HDMI6") (pin "hdmi_8") (pinfunction "hdmi_8_hdmi_8") (pintype "passive"))
    )
    (net (code "157") (name "unconnected-(HDMI6-Padhdmi_9)") (class "Default")
      (node (ref "HDMI6") (pin "hdmi_9") (pinfunction "hdmi_9_hdmi_9") (pintype "passive"))
    )
    (net (code "158") (name "unconnected-(HDMI6-Padhdmi_10)") (class "Default")
      (node (ref "HDMI6") (pin "hdmi_10") (pinfunction "hdmi_10_hdmi_10") (pintype "passive"))
    )
    (net (code "159") (name "unconnected-(HDMI6-Padhdmi_11)") (class "Default")
      (node (ref "HDMI6") (pin "hdmi_11") (pinfunction "hdmi_11_hdmi_11") (pintype "passive"))
    )
    (net (code "160") (name "unconnected-(HDMI7-Padhdmi_4)") (class "Default")
      (node (ref "HDMI7") (pin "hdmi_4") (pinfunction "hdmi_4_hdmi_4") (pintype "passive"))
    )
    (net (code "161") (name "unconnected-(HDMI7-Padhdmi_5)") (class "Default")
      (node (ref "HDMI7") (pin "hdmi_5") (pinfunction "hdmi_5_hdmi_5") (pintype "passive"))
    )
    (net (code "162") (name "unconnected-(HDMI7-Padhdmi_6)") (class "Default")
      (node (ref "HDMI7") (pin "hdmi_6") (pinfunction "hdmi_6_hdmi_6") (pintype "passive"))
    )
    (net (code "163") (name "unconnected-(HDMI7-Padhdmi_7)") (class "Default")
      (node (ref "HDMI7") (pin "hdmi_7") (pinfunction "hdmi_7_hdmi_7") (pintype "passive"))
    )
    (net (code "164") (name "unconnected-(HDMI7-Padhdmi_8)") (class "Default")
      (node (ref "HDMI7") (pin "hdmi_8") (pinfunction "hdmi_8_hdmi_8") (pintype "passive"))
    )
    (net (code "165") (name "unconnected-(HDMI7-Padhdmi_9)") (class "Default")
      (node (ref "HDMI7") (pin "hdmi_9") (pinfunction "hdmi_9_hdmi_9") (pintype "passive"))
    )
    (net (code "166") (name "unconnected-(HDMI7-Padhdmi_10)") (class "Default")
      (node (ref "HDMI7") (pin "hdmi_10") (pinfunction "hdmi_10_hdmi_10") (pintype "passive"))
    )
    (net (code "167") (name "unconnected-(HDMI7-Padhdmi_11)") (class "Default")
      (node (ref "HDMI7") (pin "hdmi_11") (pinfunction "hdmi_11_hdmi_11") (pintype "passive"))
    )
    (net (code "168") (name "unconnected-(HDMI7-Padhdmi_12)") (class "Default")
      (node (ref "HDMI7") (pin "hdmi_12") (pinfunction "hdmi_12_hdmi_12") (pintype "passive"))
    )
    (net (code "169") (name "unconnected-(HDMI8-Padhdmi_4)") (class "Default")
      (node (ref "HDMI8") (pin "hdmi_4") (pinfunction "hdmi_4_hdmi_4") (pintype "passive"))
    )
    (net (code "170") (name "unconnected-(HDMI8-Padhdmi_5)") (class "Default")
      (node (ref "HDMI8") (pin "hdmi_5") (pinfunction "hdmi_5_hdmi_5") (pintype "passive"))
    )
    (net (code "171") (name "unconnected-(HDMI8-Padhdmi_6)") (class "Default")
      (node (ref "HDMI8") (pin "hdmi_6") (pinfunction "hdmi_6_hdmi_6") (pintype "passive"))
    )
    (net (code "172") (name "unconnected-(HDMI8-Padhdmi_7)") (class "Default")
      (node (ref "HDMI8") (pin "hdmi_7") (pinfunction "hdmi_7_hdmi_7") (pintype "passive"))
    )
    (net (code "173") (name "unconnected-(HDMI8-Padhdmi_8)") (class "Default")
      (node (ref "HDMI8") (pin "hdmi_8") (pinfunction "hdmi_8_hdmi_8") (pintype "passive"))
    )
    (net (code "174") (name "unconnected-(HDMI8-Padhdmi_9)") (class "Default")
      (node (ref "HDMI8") (pin "hdmi_9") (pinfunction "hdmi_9_hdmi_9") (pintype "passive"))
    )
    (net (code "175") (name "unconnected-(HDMI8-Padhdmi_10)") (class "Default")
      (node (ref "HDMI8") (pin "hdmi_10") (pinfunction "hdmi_10_hdmi_10") (pintype "passive"))
    )
    (net (code "176") (name "unconnected-(HDMI8-Padhdmi_11)") (class "Default")
      (node (ref "HDMI8") (pin "hdmi_11") (pinfunction "hdmi_11_hdmi_11") (pintype "passive"))
    )
    (net (code "177") (name "unconnected-(HDMI8-Padhdmi_12)") (class "Default")
      (node (ref "HDMI8") (pin "hdmi_12") (pinfunction "hdmi_12_hdmi_12") (pintype "passive"))
    )
    (net (code "178") (name "unconnected-(RaspZero-Pad1)") (class "Default")
      (node (ref "RaspZero") (pin "1") (pinfunction "1_1") (pintype "passive"))
    )
    (net (code "179") (name "unconnected-(RaspZero-Pad2)") (class "Default")
      (node (ref "RaspZero") (pin "2") (pinfunction "2_2") (pintype "passive"))
    )
    (net (code "180") (name "unconnected-(RaspZero-Pad3)") (class "Default")
      (node (ref "RaspZero") (pin "3") (pinfunction "3_3") (pintype "passive"))
    )
    (net (code "181") (name "unconnected-(RaspZero-Pad4)") (class "Default")
      (node (ref "RaspZero") (pin "4") (pinfunction "4_4") (pintype "passive"))
    )
    (net (code "182") (name "unconnected-(RaspZero-Pad5)") (class "Default")
      (node (ref "RaspZero") (pin "5") (pinfunction "5_5") (pintype "passive"))
    )
    (net (code "183") (name "unconnected-(RaspZero-Pad7)") (class "Default")
      (node (ref "RaspZero") (pin "7") (pinfunction "7_7") (pintype "passive"))
    )
    (net (code "184") (name "unconnected-(RaspZero-Pad8)") (class "Default")
      (node (ref "RaspZero") (pin "8") (pinfunction "8_8") (pintype "passive"))
    )
    (net (code "185") (name "unconnected-(RaspZero-Pad10)") (class "Default")
      (node (ref "RaspZero") (pin "10") (pinfunction "10_10") (pintype "passive"))
    )
    (net (code "186") (name "unconnected-(RaspZero-Pad11)") (class "Default")
      (node (ref "RaspZero") (pin "11") (pinfunction "11_11") (pintype "passive"))
    )
    (net (code "187") (name "unconnected-(RaspZero-Pad12)") (class "Default")
      (node (ref "RaspZero") (pin "12") (pinfunction "12_12") (pintype "passive"))
    )
    (net (code "188") (name "unconnected-(RaspZero-Pad13)") (class "Default")
      (node (ref "RaspZero") (pin "13") (pinfunction "13_13") (pintype "passive"))
    )
    (net (code "189") (name "unconnected-(RaspZero-Pad15)") (class "Default")
      (node (ref "RaspZero") (pin "15") (pinfunction "15_15") (pintype "passive"))
    )
    (net (code "190") (name "unconnected-(RaspZero-Pad16)") (class "Default")
      (node (ref "RaspZero") (pin "16") (pinfunction "16_16") (pintype "passive"))
    )
    (net (code "191") (name "unconnected-(RaspZero-Pad17)") (class "Default")
      (node (ref "RaspZero") (pin "17") (pinfunction "17_17") (pintype "passive"))
    )
    (net (code "192") (name "unconnected-(RaspZero-Pad18)") (class "Default")
      (node (ref "RaspZero") (pin "18") (pinfunction "18_18") (pintype "passive"))
    )
    (net (code "193") (name "unconnected-(RaspZero-Pad19)") (class "Default")
      (node (ref "RaspZero") (pin "19") (pinfunction "19_19") (pintype "passive"))
    )
    (net (code "194") (name "unconnected-(RaspZero-Pad21)") (class "Default")
      (node (ref "RaspZero") (pin "21") (pinfunction "21_21") (pintype "passive"))
    )
    (net (code "195") (name "unconnected-(RaspZero-Pad22)") (class "Default")
      (node (ref "RaspZero") (pin "22") (pinfunction "22_22") (pintype "passive"))
    )
    (net (code "196") (name "unconnected-(RaspZero-Pad23)") (class "Default")
      (node (ref "RaspZero") (pin "23") (pinfunction "23_23") (pintype "passive"))
    )
    (net (code "197") (name "unconnected-(RaspZero-Pad24)") (class "Default")
      (node (ref "RaspZero") (pin "24") (pinfunction "24_24") (pintype "passive"))
    )
    (net (code "198") (name "unconnected-(RaspZero-Pad26)") (class "Default")
      (node (ref "RaspZero") (pin "26") (pinfunction "26_26") (pintype "passive"))
    )
    (net (code "199") (name "unconnected-(RaspZero-Pad27)") (class "Default")
      (node (ref "RaspZero") (pin "27") (pinfunction "27_27") (pintype "passive"))
    )
    (net (code "200") (name "unconnected-(RaspZero-Pad28)") (class "Default")
      (node (ref "RaspZero") (pin "28") (pinfunction "28_28") (pintype "passive"))
    )
    (net (code "201") (name "unconnected-(RaspZero-Pad29)") (class "Default")
      (node (ref "RaspZero") (pin "29") (pinfunction "29_29") (pintype "passive"))
    )
    (net (code "202") (name "unconnected-(RaspZero-Pad31)") (class "Default")
      (node (ref "RaspZero") (pin "31") (pinfunction "31_31") (pintype "passive"))
    )
    (net (code "203") (name "unconnected-(RaspZero-Pad32)") (class "Default")
      (node (ref "RaspZero") (pin "32") (pinfunction "32_32") (pintype "passive"))
    )
    (net (code "204") (name "unconnected-(RaspZero-Pad33)") (class "Default")
      (node (ref "RaspZero") (pin "33") (pinfunction "33_33") (pintype "passive"))
    )
    (net (code "205") (name "unconnected-(RaspZero-Pad35)") (class "Default")
      (node (ref "RaspZero") (pin "35") (pinfunction "35_35") (pintype "passive"))
    )
    (net (code "206") (name "unconnected-(RaspZero-Pad36)") (class "Default")
      (node (ref "RaspZero") (pin "36") (pinfunction "36_36") (pintype "passive"))
    )
    (net (code "207") (name "unconnected-(RaspZero-Pad37)") (class "Default")
      (node (ref "RaspZero") (pin "37") (pinfunction "37_37") (pintype "passive"))
    )
    (net (code "208") (name "unconnected-(RaspZero-Pad38)") (class "Default")
      (node (ref "RaspZero") (pin "38") (pinfunction "38_38") (pintype "passive"))
    )
    (net (code "209") (name "unconnected-(RaspZero-Pad40)") (class "Default")
      (node (ref "RaspZero") (pin "40") (pinfunction "40_40") (pintype "passive"))
    )
    (net (code "210") (name "unconnected-(SB10-Pad1)") (class "Default")
      (node (ref "SB10") (pin "1") (pinfunction "1_1") (pintype "passive+no_connect"))
    )
    (net (code "211") (name "unconnected-(SB11-Pad2)") (class "Default")
      (node (ref "SB11") (pin "2") (pinfunction "2_2") (pintype "passive+no_connect"))
    )
    (net (code "212") (name "unconnected-(SB14-Pad1)") (class "Default")
      (node (ref "SB14") (pin "1") (pinfunction "1_1") (pintype "passive+no_connect"))
    )
    (net (code "213") (name "unconnected-(SB15-Pad1)") (class "Default")
      (node (ref "SB15") (pin "1") (pinfunction "1_1") (pintype "passive+no_connect"))
    )
    (net (code "214") (name "unconnected-(SB115-Pad2)") (class "Default")
      (node (ref "SB115") (pin "2") (pinfunction "2_2") (pintype "passive+no_connect"))
    )
    (net (code "215") (name "unconnected-(SB121-Pad2)") (class "Default")
      (node (ref "SB121") (pin "2") (pinfunction "2_2") (pintype "passive+no_connect"))
    )
    (net (code "216") (name "unconnected-(SB122-Pad2)") (class "Default")
      (node (ref "SB122") (pin "2") (pinfunction "2_2") (pintype "passive+no_connect"))
    )
    (net (code "217") (name "unconnected-(SB126-Pad2)") (class "Default")
      (node (ref "SB126") (pin "2") (pinfunction "2_2") (pintype "passive+no_connect"))
    )
    (net (code "218") (name "unconnected-(SB128-Pad2)") (class "Default")
      (node (ref "SB128") (pin "2") (pinfunction "2_2") (pintype "passive+no_connect"))
    )
    (net (code "219") (name "unconnected-(SB130-Pad1)") (class "Default")
      (node (ref "SB130") (pin "1") (pinfunction "1_1") (pintype "passive+no_connect"))
    )
    (net (code "220") (name "unconnected-(SB131-Pad1)") (class "Default")
      (node (ref "SB131") (pin "1") (pinfunction "1_1") (pintype "passive+no_connect"))
    )
    (net (code "221") (name "unconnected-(SB134-Pad1)") (class "Default")
      (node (ref "SB134") (pin "1") (pinfunction "1_1") (pintype "passive+no_connect"))
    )
    (net (code "222") (name "unconnected-(SB135-Pad1)") (class "Default")
      (node (ref "SB135") (pin "1") (pinfunction "1_1") (pintype "passive+no_connect"))
    )
    (net (code "223") (name "unconnected-(SB136-Pad2)") (class "Default")
      (node (ref "SB136") (pin "2") (pinfunction "2_2") (pintype "passive+no_connect"))
    )
    (net (code "224") (name "unconnected-(SB137-Pad2)") (class "Default")
      (node (ref "SB137") (pin "2") (pinfunction "2_2") (pintype "passive+no_connect"))
    )
    (net (code "225") (name "unconnected-(SB138-Pad2)") (class "Default")
      (node (ref "SB138") (pin "2") (pinfunction "2_2") (pintype "passive+no_connect"))
    )
    (net (code "226") (name "unconnected-(SB140-Pad2)") (class "Default")
      (node (ref "SB140") (pin "2") (pinfunction "2_2") (pintype "passive+no_connect"))
    )
    (net (code "227") (name "unconnected-(SB141-Pad1)") (class "Default")
      (node (ref "SB141") (pin "1") (pinfunction "1_1") (pintype "passive+no_connect"))
    )
    (net (code "228") (name "unconnected-(SB143-Pad2)") (class "Default")
      (node (ref "SB143") (pin "2") (pinfunction "2_2") (pintype "passive+no_connect"))
    )
    (net (code "229") (name "unconnected-(SB146-Pad2)") (class "Default")
      (node (ref "SB146") (pin "2") (pinfunction "2_2") (pintype "passive+no_connect"))
    )
    (net (code "230") (name "unconnected-(SB147-Pad2)") (class "Default")
      (node (ref "SB147") (pin "2") (pinfunction "2_2") (pintype "passive+no_connect"))
    )
    (net (code "231") (name "unconnected-(SB150-Pad2)") (class "Default")
      (node (ref "SB150") (pin "2") (pinfunction "2_2") (pintype "passive+no_connect"))
    )
    (net (code "232") (name "unconnected-(SB151-Pad1)") (class "Default")
      (node (ref "SB151") (pin "1") (pinfunction "1_1") (pintype "passive+no_connect"))
    )
    (net (code "233") (name "unconnected-(SB157-Pad2)") (class "Default")
      (node (ref "SB157") (pin "2") (pinfunction "2_2") (pintype "passive+no_connect"))
    )
    (net (code "234") (name "unconnected-(SB158-Pad1)") (class "Default")
      (node (ref "SB158") (pin "1") (pinfunction "1_1") (pintype "passive+no_connect"))
    )
    (net (code "235") (name "unconnected-(SB159-Pad1)") (class "Default")
      (node (ref "SB159") (pin "1") (pinfunction "1_1") (pintype "passive+no_connect"))
    )
    (net (code "236") (name "unconnected-(SB165-Pad2)") (class "Default")
      (node (ref "SB165") (pin "2") (pinfunction "2_2") (pintype "passive+no_connect"))
    )
    (net (code "237") (name "unconnected-(SB167-Pad2)") (class "Default")
      (node (ref "SB167") (pin "2") (pinfunction "2_2") (pintype "passive+no_connect"))
    )
    (net (code "238") (name "unconnected-(SB168-Pad1)") (class "Default")
      (node (ref "SB168") (pin "1") (pinfunction "1_1") (pintype "passive+no_connect"))
    )
    (net (code "239") (name "unconnected-(SB169-Pad2)") (class "Default")
      (node (ref "SB169") (pin "2") (pinfunction "2_2") (pintype "passive+no_connect"))
    )
    (net (code "240") (name "unconnected-(SB170-Pad2)") (class "Default")
      (node (ref "SB170") (pin "2") (pinfunction "2_2") (pintype "passive+no_connect"))
    )
    (net (code "241") (name "unconnected-(SB171-Pad2)") (class "Default")
      (node (ref "SB171") (pin "2") (pinfunction "2_2") (pintype "passive+no_connect"))
    )
    (net (code "242") (name "unconnected-(SB172-Pad1)") (class "Default")
      (node (ref "SB172") (pin "1") (pinfunction "1_1") (pintype "passive+no_connect"))
    )
    (net (code "243") (name "unconnected-(SB174-Pad2)") (class "Default")
      (node (ref "SB174") (pin "2") (pinfunction "2_2") (pintype "passive+no_connect"))
    )
    (net (code "244") (name "unconnected-(SB175-Pad1)") (class "Default")
      (node (ref "SB175") (pin "1") (pinfunction "1_1") (pintype "passive+no_connect"))
    )
    (net (code "245") (name "unconnected-(SB176-Pad2)") (class "Default")
      (node (ref "SB176") (pin "2") (pinfunction "2_2") (pintype "passive+no_connect"))
    )
  )
)
